# TC58BVG1S3HBAI4.net
KiCad netlist of a schematic drawn in Altium Designer
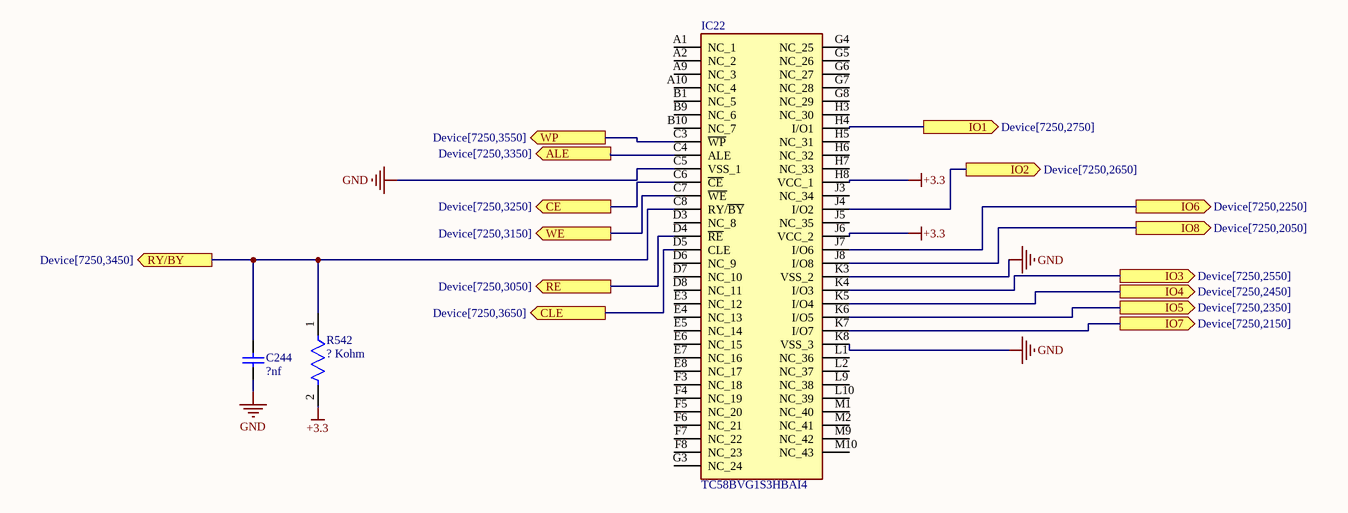
[diagram p0: TC58BVG1S3HBAI4.SchDoc]

(export (version "E")
  (design (tool "Eeschema 10.0.6"))
  (components
    (comp (ref "C244")
      (value "?nf")
      (footprint "CAPC1005X55X25NL05T10")
      (fields (field (name "MANUFACTURER") "Murata") (field (name "PART NUMBER") "GRM155F50J684ZE01D"))
      (libsource (lib "Altium Content Vault") (part "CAP"))
    )
    (comp (ref "IC22")
      (value "TC58BVG1S3HBAI4")
      (footprint "SamacSys:BGA63C80P10X12_900X1100X100")
      (description "Integrated Circuit")
      (fields (field (name "MOUSER PART NUMBER") "757-TC58BVG1S3HBAI4"))
      (libsource (lib "ReadyButNotListed") (part "TC58BVG1S3HBAI4"))
    )
    (comp (ref "R542")
      (value "? Kohm")
      (footprint "FP-RC1005-IPC_C")
      (description "Res Thick Film 0402 1.87kΩ 1% 0.063W ±100ppm/°C Molded SMD T/R")
      (fields (field (name "TOLERANCE") "1%"))
      (libsource (lib "Altium Content Vault") (part "1029c3af85768c4190bb7ad29bc67b5"))
    )
  )
  (nets
    (net (code "1") (name "+3.3") (class "Default")
      (node (ref "IC22") (pin "H8") (pinfunction "VCC_1_H8") (pintype "passive"))
      (node (ref "IC22") (pin "J6") (pinfunction "VCC_2_J6") (pintype "passive"))
      (node (ref "R542") (pin "2") (pinfunction "2_2") (pintype "passive"))
    )
    (net (code "2") (name "/ALE") (class "Default")
      (node (ref "IC22") (pin "C4") (pinfunction "ALE_C4") (pintype "passive"))
    )
    (net (code "3") (name "/CE") (class "Default")
      (node (ref "IC22") (pin "C6") (pinfunction "~{CE}_C6") (pintype "passive"))
    )
    (net (code "4") (name "/CLE") (class "Default")
      (node (ref "IC22") (pin "D5") (pinfunction "CLE_D5") (pintype "passive"))
    )
    (net (code "5") (name "/IO1") (class "Default")
      (node (ref "IC22") (pin "H4") (pinfunction "I/O1_H4") (pintype "passive"))
    )
    (net (code "6") (name "/IO2") (class "Default")
      (node (ref "IC22") (pin "J4") (pinfunction "I/O2_J4") (pintype "passive"))
    )
    (net (code "7") (name "/IO3") (class "Default")
      (node (ref "IC22") (pin "K4") (pinfunction "I/O3_K4") (pintype "passive"))
    )
    (net (code "8") (name "/IO4") (class "Default")
      (node (ref "IC22") (pin "K5") (pinfunction "I/O4_K5") (pintype "passive"))
    )
    (net (code "9") (name "/IO5") (class "Default")
      (node (ref "IC22") (pin "K6") (pinfunction "I/O5_K6") (pintype "passive"))
    )
    (net (code "10") (name "/IO6") (class "Default")
      (node (ref "IC22") (pin "J7") (pinfunction "I/O6_J7") (pintype "passive"))
    )
    (net (code "11") (name "/IO7") (class "Default")
      (node (ref "IC22") (pin "K7") (pinfunction "I/O7_K7") (pintype "passive"))
    )
    (net (code "12") (name "/IO8") (class "Default")
      (node (ref "IC22") (pin "J8") (pinfunction "I/O8_J8") (pintype "passive"))
    )
    (net (code "13") (name "/RE") (class "Default")
      (node (ref "IC22") (pin "D4") (pinfunction "~{RE}_D4") (pintype "passive"))
    )
    (net (code "14") (name "/RY{slash}BY") (class "Default")
      (node (ref "C244") (pin "2") (pinfunction "2_2") (pintype "passive"))
      (node (ref "IC22") (pin "C8") (pinfunction "RY/~{BY}_C8") (pintype "passive"))
      (node (ref "R542") (pin "1") (pinfunction "1_1") (pintype "passive"))
    )
    (net (code "15") (name "/WE") (class "Default")
      (node (ref "IC22") (pin "C7") (pinfunction "~{WE}_C7") (pintype "passive"))
    )
    (net (code "16") (name "/WP") (class "Default")
      (node (ref "IC22") (pin "C3") (pinfunction "~{WP}_C3") (pintype "passive"))
    )
    (net (code "17") (name "GND") (class "Default")
      (node (ref "C244") (pin "1") (pinfunction "1_1") (pintype "passive"))
      (node (ref "IC22") (pin "C5") (pinfunction "VSS_1_C5") (pintype "passive"))
      (node (ref "IC22") (pin "K3") (pinfunction "VSS_2_K3") (pintype "passive"))
      (node (ref "IC22") (pin "K8") (pinfunction "VSS_3_K8") (pintype "passive"))
    )
    (net (code "18") (name "unconnected-(IC22-NC_1-PadA1)") (class "Default")
      (node (ref "IC22") (pin "A1") (pinfunction "NC_1_A1") (pintype "passive"))
    )
    (net (code "19") (name "unconnected-(IC22-NC_2-PadA2)") (class "Default")
      (node (ref "IC22") (pin "A2") (pinfunction "NC_2_A2") (pintype "passive"))
    )
    (net (code "20") (name "unconnected-(IC22-NC_3-PadA9)") (class "Default")
      (node (ref "IC22") (pin "A9") (pinfunction "NC_3_A9") (pintype "passive"))
    )
    (net (code "21") (name "unconnected-(IC22-NC_4-PadA10)") (class "Default")
      (node (ref "IC22") (pin "A10") (pinfunction "NC_4_A10") (pintype "passive"))
    )
    (net (code "22") (name "unconnected-(IC22-NC_5-PadB1)") (class "Default")
      (node (ref "IC22") (pin "B1") (pinfunction "NC_5_B1") (pintype "passive"))
    )
    (net (code "23") (name "unconnected-(IC22-NC_6-PadB9)") (class "Default")
      (node (ref "IC22") (pin "B9") (pinfunction "NC_6_B9") (pintype "passive"))
    )
    (net (code "24") (name "unconnected-(IC22-NC_7-PadB10)") (class "Default")
      (node (ref "IC22") (pin "B10") (pinfunction "NC_7_B10") (pintype "passive"))
    )
    (net (code "25") (name "unconnected-(IC22-NC_8-PadD3)") (class "Default")
      (node (ref "IC22") (pin "D3") (pinfunction "NC_8_D3") (pintype "passive"))
    )
    (net (code "26") (name "unconnected-(IC22-NC_9-PadD6)") (class "Default")
      (node (ref "IC22") (pin "D6") (pinfunction "NC_9_D6") (pintype "passive"))
    )
    (net (code "27") (name "unconnected-(IC22-NC_10-PadD7)") (class "Default")
      (node (ref "IC22") (pin "D7") (pinfunction "NC_10_D7") (pintype "passive"))
    )
    (net (code "28") (name "unconnected-(IC22-NC_11-PadD8)") (class "Default")
      (node (ref "IC22") (pin "D8") (pinfunction "NC_11_D8") (pintype "passive"))
    )
    (net (code "29") (name "unconnected-(IC22-NC_12-PadE3)") (class "Default")
      (node (ref "IC22") (pin "E3") (pinfunction "NC_12_E3") (pintype "passive"))
    )
    (net (code "30") (name "unconnected-(IC22-NC_13-PadE4)") (class "Default")
      (node (ref "IC22") (pin "E4") (pinfunction "NC_13_E4") (pintype "passive"))
    )
    (net (code "31") (name "unconnected-(IC22-NC_14-PadE5)") (class "Default")
      (node (ref "IC22") (pin "E5") (pinfunction "NC_14_E5") (pintype "passive"))
    )
    (net (code "32") (name "unconnected-(IC22-NC_15-PadE6)") (class "Default")
      (node (ref "IC22") (pin "E6") (pinfunction "NC_15_E6") (pintype "passive"))
    )
    (net (code "33") (name "unconnected-(IC22-NC_16-PadE7)") (class "Default")
      (node (ref "IC22") (pin "E7") (pinfunction "NC_16_E7") (pintype "passive"))
    )
    (net (code "34") (name "unconnected-(IC22-NC_17-PadE8)") (class "Default")
      (node (ref "IC22") (pin "E8") (pinfunction "NC_17_E8") (pintype "passive"))
    )
    (net (code "35") (name "unconnected-(IC22-NC_18-PadF3)") (class "Default")
      (node (ref "IC22") (pin "F3") (pinfunction "NC_18_F3") (pintype "passive"))
    )
    (net (code "36") (name "unconnected-(IC22-NC_19-PadF4)") (class "Default")
      (node (ref "IC22") (pin "F4") (pinfunction "NC_19_F4") (pintype "passive"))
    )
    (net (code "37") (name "unconnected-(IC22-NC_20-PadF5)") (class "Default")
      (node (ref "IC22") (pin "F5") (pinfunction "NC_20_F5") (pintype "passive"))
    )
    (net (code "38") (name "unconnected-(IC22-NC_21-PadF6)") (class "Default")
      (node (ref "IC22") (pin "F6") (pinfunction "NC_21_F6") (pintype "passive"))
    )
    (net (code "39") (name "unconnected-(IC22-NC_22-PadF7)") (class "Default")
      (node (ref "IC22") (pin "F7") (pinfunction "NC_22_F7") (pintype "passive"))
    )
    (net (code "40") (name "unconnected-(IC22-NC_23-PadF8)") (class "Default")
      (node (ref "IC22") (pin "F8") (pinfunction "NC_23_F8") (pintype "passive"))
    )
    (net (code "41") (name "unconnected-(IC22-NC_24-PadG3)") (class "Default")
      (node (ref "IC22") (pin "G3") (pinfunction "NC_24_G3") (pintype "passive"))
    )
    (net (code "42") (name "unconnected-(IC22-NC_25-PadG4)") (class "Default")
      (node (ref "IC22") (pin "G4") (pinfunction "NC_25_G4") (pintype "passive"))
    )
    (net (code "43") (name "unconnected-(IC22-NC_26-PadG5)") (class "Default")
      (node (ref "IC22") (pin "G5") (pinfunction "NC_26_G5") (pintype "passive"))
    )
    (net (code "44") (name "unconnected-(IC22-NC_27-PadG6)") (class "Default")
      (node (ref "IC22") (pin "G6") (pinfunction "NC_27_G6") (pintype "passive"))
    )
    (net (code "45") (name "unconnected-(IC22-NC_28-PadG7)") (class "Default")
      (node (ref "IC22") (pin "G7") (pinfunction "NC_28_G7") (pintype "passive"))
    )
    (net (code "46") (name "unconnected-(IC22-NC_29-PadG8)") (class "Default")
      (node (ref "IC22") (pin "G8") (pinfunction "NC_29_G8") (pintype "passive"))
    )
    (net (code "47") (name "unconnected-(IC22-NC_30-PadH3)") (class "Default")
      (node (ref "IC22") (pin "H3") (pinfunction "NC_30_H3") (pintype "passive"))
    )
    (net (code "48") (name "unconnected-(IC22-NC_31-PadH5)") (class "Default")
      (node (ref "IC22") (pin "H5") (pinfunction "NC_31_H5") (pintype "passive"))
    )
    (net (code "49") (name "unconnected-(IC22-NC_32-PadH6)") (class "Default")
      (node (ref "IC22") (pin "H6") (pinfunction "NC_32_H6") (pintype "passive"))
    )
    (net (code "50") (name "unconnected-(IC22-NC_33-PadH7)") (class "Default")
      (node (ref "IC22") (pin "H7") (pinfunction "NC_33_H7") (pintype "passive"))
    )
    (net (code "51") (name "unconnected-(IC22-NC_34-PadJ3)") (class "Default")
      (node (ref "IC22") (pin "J3") (pinfunction "NC_34_J3") (pintype "passive"))
    )
    (net (code "52") (name "unconnected-(IC22-NC_35-PadJ5)") (class "Default")
      (node (ref "IC22") (pin "J5") (pinfunction "NC_35_J5") (pintype "passive"))
    )
    (net (code "53") (name "unconnected-(IC22-NC_36-PadL1)") (class "Default")
      (node (ref "IC22") (pin "L1") (pinfunction "NC_36_L1") (pintype "passive"))
    )
    (net (code "54") (name "unconnected-(IC22-NC_37-PadL2)") (class "Default")
      (node (ref "IC22") (pin "L2") (pinfunction "NC_37_L2") (pintype "passive"))
    )
    (net (code "55") (name "unconnected-(IC22-NC_38-PadL9)") (class "Default")
      (node (ref "IC22") (pin "L9") (pinfunction "NC_38_L9") (pintype "passive"))
    )
    (net (code "56") (name "unconnected-(IC22-NC_39-PadL10)") (class "Default")
      (node (ref "IC22") (pin "L10") (pinfunction "NC_39_L10") (pintype "passive"))
    )
    (net (code "57") (name "unconnected-(IC22-NC_40-PadM1)") (class "Default")
      (node (ref "IC22") (pin "M1") (pinfunction "NC_40_M1") (pintype "passive"))
    )
    (net (code "58") (name "unconnected-(IC22-NC_41-PadM2)") (class "Default")
      (node (ref "IC22") (pin "M2") (pinfunction "NC_41_M2") (pintype "passive"))
    )
    (net (code "59") (name "unconnected-(IC22-NC_42-PadM9)") (class "Default")
      (node (ref "IC22") (pin "M9") (pinfunction "NC_42_M9") (pintype "passive"))
    )
    (net (code "60") (name "unconnected-(IC22-NC_43-PadM10)") (class "Default")
      (node (ref "IC22") (pin "M10") (pinfunction "NC_43_M10") (pintype "passive"))
    )
  )
)
